# Arm_Driver.net
KiCad netlist of a schematic drawn in EAGLE
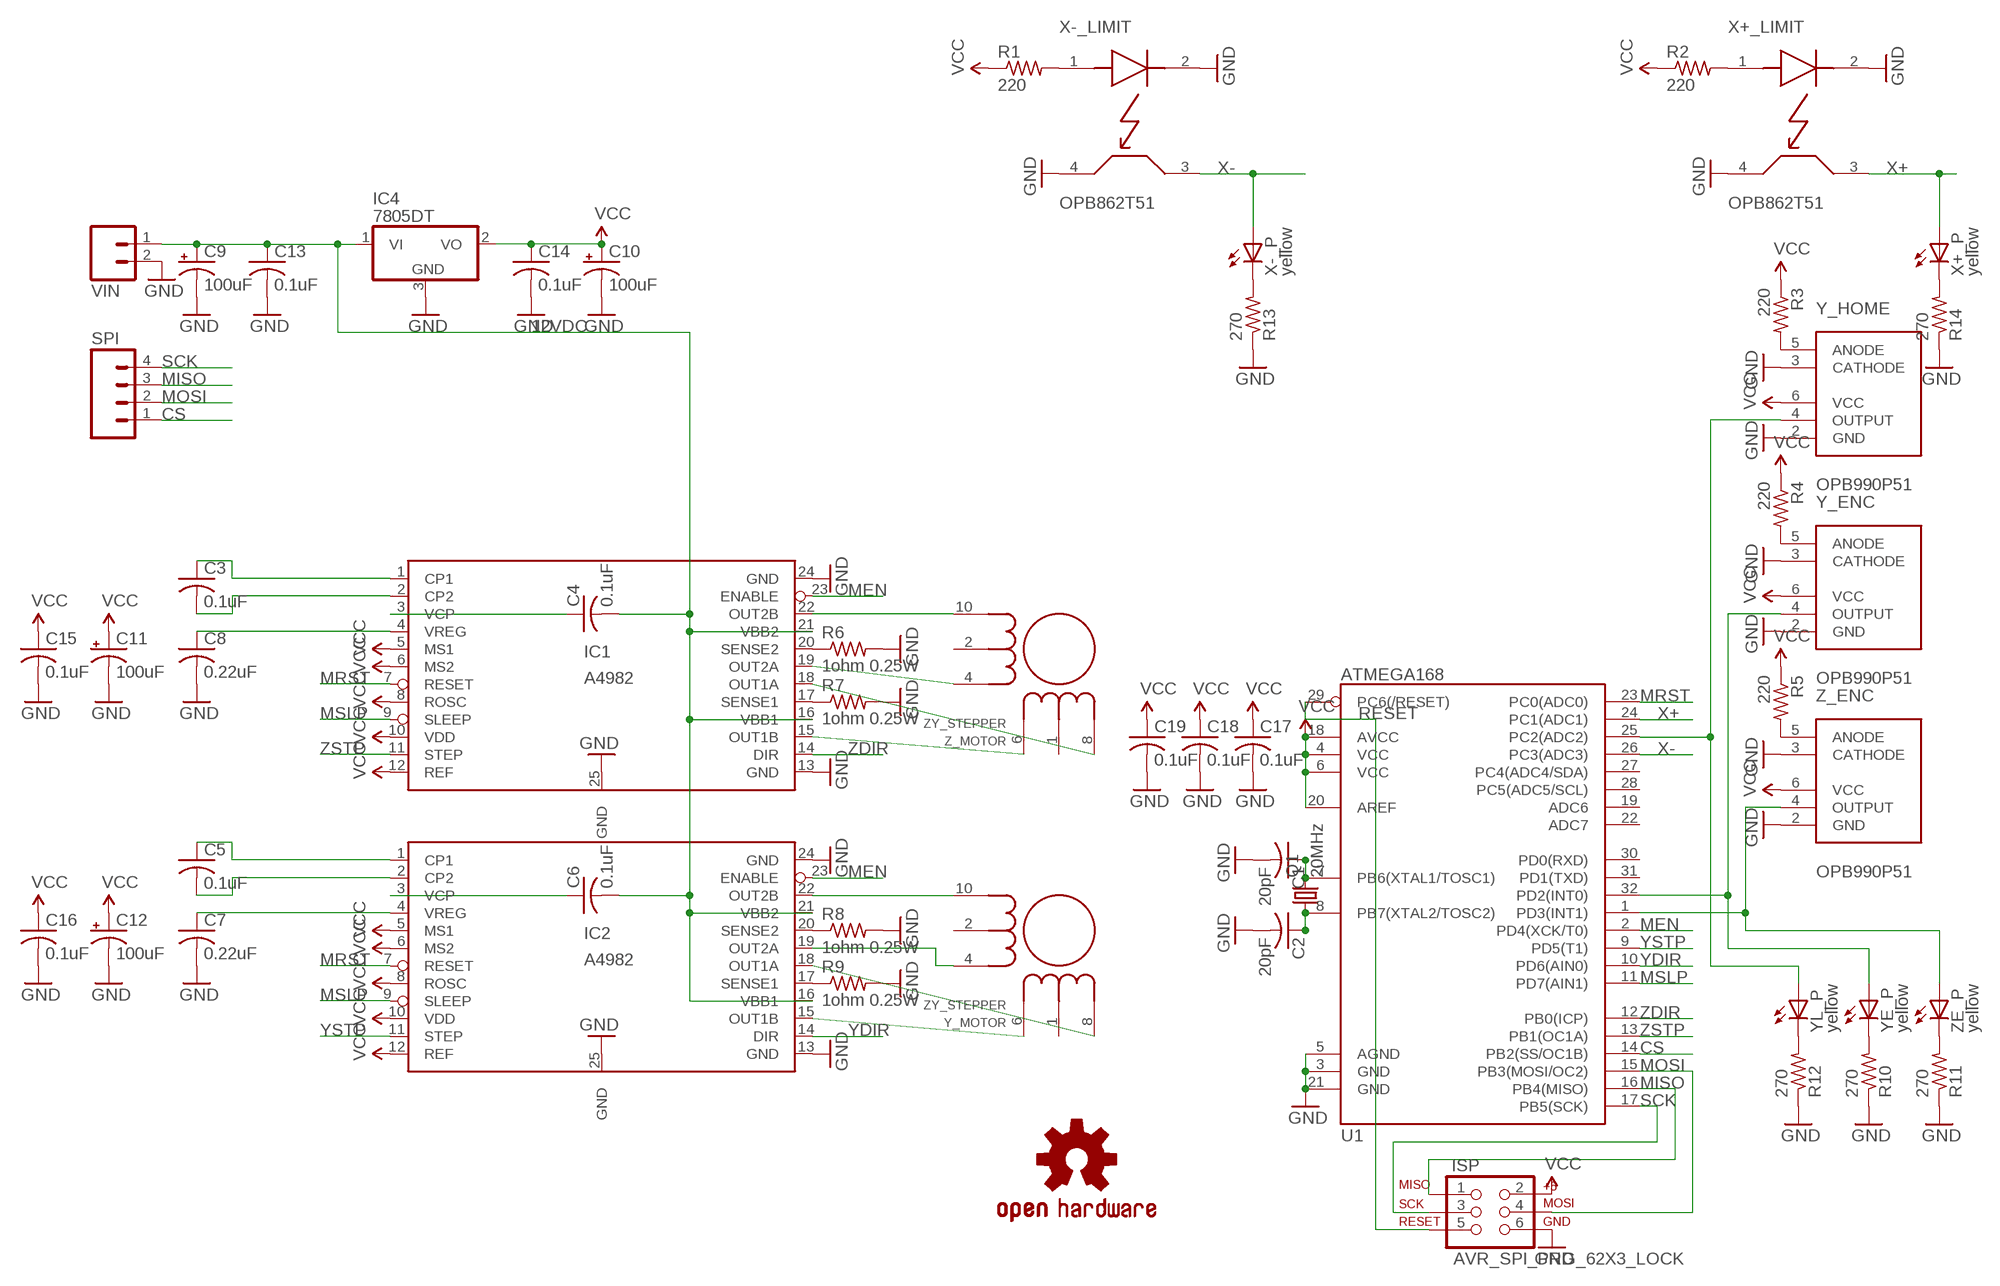
[diagram p0: schematic, sheet 1]

(export (version "E")
  (design (tool "Eeschema 10.0.6"))
  (components
    (comp (ref "C1")
      (value "20pF")
      (footprint "eagle-import:C0603")
      (libsource (lib "eagle-import") (part "C-USC0603"))
    )
    (comp (ref "C2")
      (value "20pF")
      (footprint "eagle-import:C0603")
      (libsource (lib "eagle-import") (part "C-USC0603"))
    )
    (comp (ref "C3")
      (value "0.1uF")
      (footprint "eagle-import:C0603")
      (libsource (lib "eagle-import") (part "C-USC0603"))
    )
    (comp (ref "C4")
      (value "0.1uF")
      (footprint "eagle-import:C0603")
      (libsource (lib "eagle-import") (part "C-USC0603"))
    )
    (comp (ref "C5")
      (value "0.1uF")
      (footprint "eagle-import:C0603")
      (libsource (lib "eagle-import") (part "C-USC0603"))
    )
    (comp (ref "C6")
      (value "0.1uF")
      (footprint "eagle-import:C0603")
      (libsource (lib "eagle-import") (part "C-USC0603"))
    )
    (comp (ref "C7")
      (value "0.22uF")
      (footprint "eagle-import:C0603")
      (libsource (lib "eagle-import") (part "C-USC0603"))
    )
    (comp (ref "C8")
      (value "0.22uF")
      (footprint "eagle-import:C0603")
      (libsource (lib "eagle-import") (part "C-USC0603"))
    )
    (comp (ref "C9")
      (value "100uF")
      (footprint "eagle-import:153CLV-0505")
      (libsource (lib "eagle-import") (part "CPOL-US153CLV-0505"))
    )
    (comp (ref "C10")
      (value "100uF")
      (footprint "eagle-import:153CLV-0505")
      (libsource (lib "eagle-import") (part "CPOL-US153CLV-0505"))
    )
    (comp (ref "C11")
      (value "100uF")
      (footprint "eagle-import:153CLV-0505")
      (libsource (lib "eagle-import") (part "CPOL-US153CLV-0505"))
    )
    (comp (ref "C12")
      (value "100uF")
      (footprint "eagle-import:153CLV-0505")
      (libsource (lib "eagle-import") (part "CPOL-US153CLV-0505"))
    )
    (comp (ref "C13")
      (value "0.1uF")
      (footprint "eagle-import:C0603")
      (libsource (lib "eagle-import") (part "C-USC0603"))
    )
    (comp (ref "C14")
      (value "0.1uF")
      (footprint "eagle-import:C0603")
      (libsource (lib "eagle-import") (part "C-USC0603"))
    )
    (comp (ref "C15")
      (value "0.1uF")
      (footprint "eagle-import:C0603")
      (libsource (lib "eagle-import") (part "C-USC0603"))
    )
    (comp (ref "C16")
      (value "0.1uF")
      (footprint "eagle-import:C0603")
      (libsource (lib "eagle-import") (part "C-USC0603"))
    )
    (comp (ref "C17")
      (value "0.1uF")
      (footprint "eagle-import:C0603")
      (libsource (lib "eagle-import") (part "C-USC0603"))
    )
    (comp (ref "C18")
      (value "0.1uF")
      (footprint "eagle-import:C0603")
      (libsource (lib "eagle-import") (part "C-USC0603"))
    )
    (comp (ref "C19")
      (value "0.1uF")
      (footprint "eagle-import:C0603")
      (libsource (lib "eagle-import") (part "C-USC0603"))
    )
    (comp (ref "IC1")
      (value "A4982")
      (footprint "eagle-import:24TSSOP")
      (libsource (lib "eagle-import") (part "A4982"))
    )
    (comp (ref "IC2")
      (value "A4982")
      (footprint "eagle-import:24TSSOP")
      (libsource (lib "eagle-import") (part "A4982"))
    )
    (comp (ref "IC4")
      (value "7805DT")
      (footprint "eagle-import:TO252")
      (libsource (lib "eagle-import") (part "78DT05"))
    )
    (comp (ref "ISP")
      (value "AVR_SPI_PRG_62X3_LOCK")
      (footprint "eagle-import:2X3_LOCK")
      (libsource (lib "eagle-import") (part "AVR_SPI_PRG_62X3_LOCK"))
    )
    (comp (ref "Q1")
      (value "20MHz")
      (footprint "eagle-import:HC49UP")
      (libsource (lib "eagle-import") (part "CRYSTALHC49UP"))
    )
    (comp (ref "R1")
      (value "220")
      (footprint "eagle-import:R0603")
      (libsource (lib "eagle-import") (part "R-US_R0603"))
    )
    (comp (ref "R2")
      (value "220")
      (footprint "eagle-import:R0603")
      (libsource (lib "eagle-import") (part "R-US_R0603"))
    )
    (comp (ref "R3")
      (value "220")
      (footprint "eagle-import:R0603")
      (libsource (lib "eagle-import") (part "R-US_R0603"))
    )
    (comp (ref "R4")
      (value "220")
      (footprint "eagle-import:R0603")
      (libsource (lib "eagle-import") (part "R-US_R0603"))
    )
    (comp (ref "R5")
      (value "220")
      (footprint "eagle-import:R0603")
      (libsource (lib "eagle-import") (part "R-US_R0603"))
    )
    (comp (ref "R6")
      (value "1ohm 0.25W")
      (footprint "eagle-import:R0603")
      (libsource (lib "eagle-import") (part "R-US_R0603"))
    )
    (comp (ref "R7")
      (value "1ohm 0.25W")
      (footprint "eagle-import:R0603")
      (libsource (lib "eagle-import") (part "R-US_R0603"))
    )
    (comp (ref "R8")
      (value "1ohm 0.25W")
      (footprint "eagle-import:R0603")
      (libsource (lib "eagle-import") (part "R-US_R0603"))
    )
    (comp (ref "R9")
      (value "1ohm 0.25W")
      (footprint "eagle-import:R0603")
      (libsource (lib "eagle-import") (part "R-US_R0603"))
    )
    (comp (ref "R10")
      (value "270")
      (footprint "eagle-import:R0603")
      (libsource (lib "eagle-import") (part "R-US_R0603"))
    )
    (comp (ref "R11")
      (value "270")
      (footprint "eagle-import:R0603")
      (libsource (lib "eagle-import") (part "R-US_R0603"))
    )
    (comp (ref "R12")
      (value "270")
      (footprint "eagle-import:R0603")
      (libsource (lib "eagle-import") (part "R-US_R0603"))
    )
    (comp (ref "R13")
      (value "270")
      (footprint "eagle-import:R0603")
      (libsource (lib "eagle-import") (part "R-US_R0603"))
    )
    (comp (ref "R14")
      (value "270")
      (footprint "eagle-import:R0603")
      (libsource (lib "eagle-import") (part "R-US_R0603"))
    )
    (comp (ref "SPI")
      (value "M04LOCK")
      (footprint "eagle-import:1X04_LOCK")
      (libsource (lib "eagle-import") (part "M04LOCK"))
    )
    (comp (ref "U$1")
      (value "OSHW-LOGOM")
      (footprint "eagle-import:OSHW-LOGO-M")
      (libsource (lib "eagle-import") (part "OSHW-LOGOM"))
    )
    (comp (ref "U1")
      (value "ATMEGA168")
      (footprint "eagle-import:TQFP32-08")
      (libsource (lib "eagle-import") (part "ATMEGA168"))
    )
    (comp (ref "VIN")
      (value "M025MM")
      (footprint "eagle-import:SCREWTERMINAL-5MM-2")
      (libsource (lib "eagle-import") (part "M025MM"))
    )
    (comp (ref "X+_LIMIT")
      (value "OPB862T51")
      (footprint "eagle-import:OPB862T51")
      (libsource (lib "eagle-import") (part "OPB862T51"))
    )
    (comp (ref "X+_P")
      (value "yellow")
      (footprint "eagle-import:CHIP-LED0603")
      (libsource (lib "eagle-import") (part "LEDCHIP-LED0603"))
    )
    (comp (ref "X-_LIMIT")
      (value "OPB862T51")
      (footprint "eagle-import:OPB862T51")
      (libsource (lib "eagle-import") (part "OPB862T51"))
    )
    (comp (ref "X-_P")
      (value "yellow")
      (footprint "eagle-import:CHIP-LED0603")
      (libsource (lib "eagle-import") (part "LEDCHIP-LED0603"))
    )
    (comp (ref "YE_P")
      (value "yellow")
      (footprint "eagle-import:CHIP-LED0603")
      (libsource (lib "eagle-import") (part "LEDCHIP-LED0603"))
    )
    (comp (ref "YL_P")
      (value "yellow")
      (footprint "eagle-import:CHIP-LED0603")
      (libsource (lib "eagle-import") (part "LEDCHIP-LED0603"))
    )
    (comp (ref "Y_ENC")
      (value "OPB990P51")
      (footprint "eagle-import:OPB990P51")
      (libsource (lib "eagle-import") (part "OPB990P51"))
    )
    (comp (ref "Y_HOME")
      (value "OPB990P51")
      (footprint "eagle-import:OPB990P51")
      (libsource (lib "eagle-import") (part "OPB990P51"))
    )
    (comp (ref "Y_MOTOR")
      (value "ZY_STEPPER")
      (footprint "eagle-import:2X5_SHROUDED")
      (libsource (lib "eagle-import") (part "ZY_STEPPER"))
    )
    (comp (ref "ZE_P")
      (value "yellow")
      (footprint "eagle-import:CHIP-LED0603")
      (libsource (lib "eagle-import") (part "LEDCHIP-LED0603"))
    )
    (comp (ref "Z_ENC")
      (value "OPB990P51")
      (footprint "eagle-import:OPB990P51")
      (libsource (lib "eagle-import") (part "OPB990P51"))
    )
    (comp (ref "Z_MOTOR")
      (value "ZY_STEPPER")
      (footprint "eagle-import:2X5_SHROUDED")
      (libsource (lib "eagle-import") (part "ZY_STEPPER"))
    )
  )
  (nets
    (net (code "1") (name "/12VDC") (class "Default")
      (node (ref "C13") (pin "1") (pinfunction "1_1") (pintype "passive"))
      (node (ref "C4") (pin "2") (pinfunction "2_2") (pintype "passive"))
      (node (ref "C6") (pin "2") (pinfunction "2_2") (pintype "passive"))
      (node (ref "C9") (pin "+") (pinfunction "+_+") (pintype "passive"))
      (node (ref "IC1") (pin "16") (pinfunction "VBB1_16") (pintype "power_in"))
      (node (ref "IC1") (pin "21") (pinfunction "VBB2_21") (pintype "power_in"))
      (node (ref "IC2") (pin "16") (pinfunction "VBB1_16") (pintype "power_in"))
      (node (ref "IC2") (pin "21") (pinfunction "VBB2_21") (pintype "power_in"))
      (node (ref "IC4") (pin "1") (pinfunction "VI_1") (pintype "input"))
      (node (ref "VIN") (pin "1") (pinfunction "1_1") (pintype "passive"))
    )
    (net (code "2") (name "/CS") (class "Default")
      (node (ref "SPI") (pin "1") (pinfunction "1_1") (pintype "passive"))
      (node (ref "U1") (pin "14") (pinfunction "PB2(SS/OC1B)_14") (pintype "bidirectional"))
    )
    (net (code "3") (name "/MEN") (class "Default")
      (node (ref "IC1") (pin "23") (pinfunction "ENABLE_23") (pintype "input"))
      (node (ref "IC2") (pin "23") (pinfunction "ENABLE_23") (pintype "input"))
      (node (ref "U1") (pin "2") (pinfunction "PD4(XCK/T0)_2") (pintype "bidirectional"))
    )
    (net (code "4") (name "/MISO") (class "Default")
      (node (ref "ISP") (pin "1") (pinfunction "1_1") (pintype "passive"))
      (node (ref "SPI") (pin "3") (pinfunction "3_3") (pintype "passive"))
      (node (ref "U1") (pin "16") (pinfunction "PB4(MISO)_16") (pintype "bidirectional"))
    )
    (net (code "5") (name "/MOSI") (class "Default")
      (node (ref "ISP") (pin "4") (pinfunction "4_4") (pintype "passive"))
      (node (ref "SPI") (pin "2") (pinfunction "2_2") (pintype "passive"))
      (node (ref "U1") (pin "15") (pinfunction "PB3(MOSI/OC2)_15") (pintype "bidirectional"))
    )
    (net (code "6") (name "/MRST") (class "Default")
      (node (ref "IC1") (pin "7") (pinfunction "RESET_7") (pintype "input"))
      (node (ref "IC2") (pin "7") (pinfunction "RESET_7") (pintype "input"))
      (node (ref "U1") (pin "23") (pinfunction "PC0(ADC0)_23") (pintype "bidirectional"))
    )
    (net (code "7") (name "/MSLP") (class "Default")
      (node (ref "IC1") (pin "9") (pinfunction "SLEEP_9") (pintype "input"))
      (node (ref "IC2") (pin "9") (pinfunction "SLEEP_9") (pintype "input"))
      (node (ref "U1") (pin "11") (pinfunction "PD7(AIN1)_11") (pintype "bidirectional"))
    )
    (net (code "8") (name "/RESET") (class "Default")
      (node (ref "ISP") (pin "5") (pinfunction "5_5") (pintype "passive"))
      (node (ref "U1") (pin "29") (pinfunction "PC6(/RESET)_29") (pintype "bidirectional"))
    )
    (net (code "9") (name "/SCK") (class "Default")
      (node (ref "ISP") (pin "3") (pinfunction "3_3") (pintype "passive"))
      (node (ref "SPI") (pin "4") (pinfunction "4_4") (pintype "passive"))
      (node (ref "U1") (pin "17") (pinfunction "PB5(SCK)_17") (pintype "bidirectional"))
    )
    (net (code "10") (name "/X+") (class "Default")
      (node (ref "U1") (pin "24") (pinfunction "PC1(ADC1)_24") (pintype "bidirectional"))
      (node (ref "X+_LIMIT") (pin "3") (pinfunction "COLLECTOR_3") (pintype "bidirectional"))
      (node (ref "X+_P") (pin "A") (pinfunction "A_A") (pintype "passive"))
    )
    (net (code "11") (name "/X-") (class "Default")
      (node (ref "U1") (pin "26") (pinfunction "PC3(ADC3)_26") (pintype "bidirectional"))
      (node (ref "X-_LIMIT") (pin "3") (pinfunction "COLLECTOR_3") (pintype "bidirectional"))
      (node (ref "X-_P") (pin "A") (pinfunction "A_A") (pintype "passive"))
    )
    (net (code "12") (name "/YDIR") (class "Default")
      (node (ref "IC2") (pin "14") (pinfunction "DIR_14") (pintype "input"))
      (node (ref "U1") (pin "10") (pinfunction "PD6(AIN0)_10") (pintype "bidirectional"))
    )
    (net (code "13") (name "/YSTP") (class "Default")
      (node (ref "IC2") (pin "11") (pinfunction "STEP_11") (pintype "input"))
      (node (ref "U1") (pin "9") (pinfunction "PD5(T1)_9") (pintype "bidirectional"))
    )
    (net (code "14") (name "/ZDIR") (class "Default")
      (node (ref "IC1") (pin "14") (pinfunction "DIR_14") (pintype "input"))
      (node (ref "U1") (pin "12") (pinfunction "PB0(ICP)_12") (pintype "bidirectional"))
    )
    (net (code "15") (name "/ZSTP") (class "Default")
      (node (ref "IC1") (pin "11") (pinfunction "STEP_11") (pintype "input"))
      (node (ref "U1") (pin "13") (pinfunction "PB1(OC1A)_13") (pintype "bidirectional"))
    )
    (net (code "16") (name "GND") (class "Default")
      (node (ref "C1") (pin "2") (pinfunction "2_2") (pintype "passive"))
      (node (ref "C10") (pin "-") (pinfunction "-_-") (pintype "passive"))
      (node (ref "C11") (pin "-") (pinfunction "-_-") (pintype "passive"))
      (node (ref "C12") (pin "-") (pinfunction "-_-") (pintype "passive"))
      (node (ref "C13") (pin "2") (pinfunction "2_2") (pintype "passive"))
      (node (ref "C14") (pin "2") (pinfunction "2_2") (pintype "passive"))
      (node (ref "C15") (pin "2") (pinfunction "2_2") (pintype "passive"))
      (node (ref "C16") (pin "2") (pinfunction "2_2") (pintype "passive"))
      (node (ref "C17") (pin "2") (pinfunction "2_2") (pintype "passive"))
      (node (ref "C18") (pin "2") (pinfunction "2_2") (pintype "passive"))
      (node (ref "C19") (pin "2") (pinfunction "2_2") (pintype "passive"))
      (node (ref "C2") (pin "2") (pinfunction "2_2") (pintype "passive"))
      (node (ref "C7") (pin "2") (pinfunction "2_2") (pintype "passive"))
      (node (ref "C8") (pin "2") (pinfunction "2_2") (pintype "passive"))
      (node (ref "C9") (pin "-") (pinfunction "-_-") (pintype "passive"))
      (node (ref "IC1") (pin "13") (pinfunction "GND_13") (pintype "power_in"))
      (node (ref "IC1") (pin "24") (pinfunction "GND_24") (pintype "power_in"))
      (node (ref "IC1") (pin "25") (pinfunction "GND_25") (pintype "power_in"))
      (node (ref "IC2") (pin "13") (pinfunction "GND_13") (pintype "power_in"))
      (node (ref "IC2") (pin "24") (pinfunction "GND_24") (pintype "power_in"))
      (node (ref "IC2") (pin "25") (pinfunction "GND_25") (pintype "power_in"))
      (node (ref "IC4") (pin "3") (pinfunction "GND_3") (pintype "passive"))
      (node (ref "ISP") (pin "6") (pinfunction "6_6") (pintype "passive"))
      (node (ref "R10") (pin "1") (pinfunction "1_1") (pintype "passive"))
      (node (ref "R11") (pin "1") (pinfunction "1_1") (pintype "passive"))
      (node (ref "R12") (pin "1") (pinfunction "1_1") (pintype "passive"))
      (node (ref "R13") (pin "1") (pinfunction "1_1") (pintype "passive"))
      (node (ref "R14") (pin "1") (pinfunction "1_1") (pintype "passive"))
      (node (ref "R6") (pin "2") (pinfunction "2_2") (pintype "passive"))
      (node (ref "R7") (pin "2") (pinfunction "2_2") (pintype "passive"))
      (node (ref "R8") (pin "2") (pinfunction "2_2") (pintype "passive"))
      (node (ref "R9") (pin "2") (pinfunction "2_2") (pintype "passive"))
      (node (ref "U1") (pin "21") (pinfunction "GND_21") (pintype "bidirectional"))
      (node (ref "U1") (pin "3") (pinfunction "GND_3") (pintype "bidirectional"))
      (node (ref "U1") (pin "5") (pinfunction "AGND_5") (pintype "bidirectional"))
      (node (ref "VIN") (pin "2") (pinfunction "2_2") (pintype "passive"))
      (node (ref "X+_LIMIT") (pin "2") (pinfunction "CATHODE_2") (pintype "bidirectional"))
      (node (ref "X+_LIMIT") (pin "4") (pinfunction "EMITTER_4") (pintype "bidirectional"))
      (node (ref "X-_LIMIT") (pin "2") (pinfunction "CATHODE_2") (pintype "bidirectional"))
      (node (ref "X-_LIMIT") (pin "4") (pinfunction "EMITTER_4") (pintype "bidirectional"))
      (node (ref "Y_ENC") (pin "2") (pinfunction "GND_2") (pintype "bidirectional"))
      (node (ref "Y_ENC") (pin "3") (pinfunction "CATHODE_3") (pintype "bidirectional"))
      (node (ref "Y_HOME") (pin "2") (pinfunction "GND_2") (pintype "bidirectional"))
      (node (ref "Y_HOME") (pin "3") (pinfunction "CATHODE_3") (pintype "bidirectional"))
      (node (ref "Z_ENC") (pin "2") (pinfunction "GND_2") (pintype "bidirectional"))
      (node (ref "Z_ENC") (pin "3") (pinfunction "CATHODE_3") (pintype "bidirectional"))
    )
    (net (code "17") (name "Net-(IC1-CP1)") (class "Default")
      (node (ref "C3") (pin "1") (pinfunction "1_1") (pintype "passive"))
      (node (ref "IC1") (pin "1") (pinfunction "CP1_1") (pintype "bidirectional"))
    )
    (net (code "18") (name "Net-(IC1-CP2)") (class "Default")
      (node (ref "C3") (pin "2") (pinfunction "2_2") (pintype "passive"))
      (node (ref "IC1") (pin "2") (pinfunction "CP2_2") (pintype "bidirectional"))
    )
    (net (code "19") (name "Net-(IC1-OUT1A)") (class "Default")
      (node (ref "IC1") (pin "18") (pinfunction "OUT1A_18") (pintype "output"))
      (node (ref "Z_MOTOR") (pin "8") (pinfunction "A1_8") (pintype "bidirectional"))
    )
    (net (code "20") (name "Net-(IC1-OUT1B)") (class "Default")
      (node (ref "IC1") (pin "15") (pinfunction "OUT1B_15") (pintype "output"))
      (node (ref "Z_MOTOR") (pin "6") (pinfunction "A2_6") (pintype "bidirectional"))
    )
    (net (code "21") (name "Net-(IC1-OUT2A)") (class "Default")
      (node (ref "IC1") (pin "19") (pinfunction "OUT2A_19") (pintype "output"))
      (node (ref "Z_MOTOR") (pin "4") (pinfunction "B1_4") (pintype "bidirectional"))
    )
    (net (code "22") (name "Net-(IC1-OUT2B)") (class "Default")
      (node (ref "IC1") (pin "22") (pinfunction "OUT2B_22") (pintype "output"))
      (node (ref "Z_MOTOR") (pin "10") (pinfunction "B2_10") (pintype "bidirectional"))
    )
    (net (code "23") (name "Net-(IC1-SENSE1)") (class "Default")
      (node (ref "IC1") (pin "17") (pinfunction "SENSE1_17") (pintype "input"))
      (node (ref "R7") (pin "1") (pinfunction "1_1") (pintype "passive"))
    )
    (net (code "24") (name "Net-(IC1-SENSE2)") (class "Default")
      (node (ref "IC1") (pin "20") (pinfunction "SENSE2_20") (pintype "input"))
      (node (ref "R6") (pin "1") (pinfunction "1_1") (pintype "passive"))
    )
    (net (code "25") (name "Net-(IC1-VCP)") (class "Default")
      (node (ref "C4") (pin "1") (pinfunction "1_1") (pintype "passive"))
      (node (ref "IC1") (pin "3") (pinfunction "VCP_3") (pintype "bidirectional"))
    )
    (net (code "26") (name "Net-(IC1-VREG)") (class "Default")
      (node (ref "C8") (pin "1") (pinfunction "1_1") (pintype "passive"))
      (node (ref "IC1") (pin "4") (pinfunction "VREG_4") (pintype "bidirectional"))
    )
    (net (code "27") (name "Net-(IC2-CP1)") (class "Default")
      (node (ref "C5") (pin "1") (pinfunction "1_1") (pintype "passive"))
      (node (ref "IC2") (pin "1") (pinfunction "CP1_1") (pintype "bidirectional"))
    )
    (net (code "28") (name "Net-(IC2-CP2)") (class "Default")
      (node (ref "C5") (pin "2") (pinfunction "2_2") (pintype "passive"))
      (node (ref "IC2") (pin "2") (pinfunction "CP2_2") (pintype "bidirectional"))
    )
    (net (code "29") (name "Net-(IC2-OUT1A)") (class "Default")
      (node (ref "IC2") (pin "18") (pinfunction "OUT1A_18") (pintype "output"))
      (node (ref "Y_MOTOR") (pin "8") (pinfunction "A1_8") (pintype "bidirectional"))
    )
    (net (code "30") (name "Net-(IC2-OUT1B)") (class "Default")
      (node (ref "IC2") (pin "15") (pinfunction "OUT1B_15") (pintype "output"))
      (node (ref "Y_MOTOR") (pin "6") (pinfunction "A2_6") (pintype "bidirectional"))
    )
    (net (code "31") (name "Net-(IC2-OUT2A)") (class "Default")
      (node (ref "IC2") (pin "19") (pinfunction "OUT2A_19") (pintype "output"))
      (node (ref "Y_MOTOR") (pin "4") (pinfunction "B1_4") (pintype "bidirectional"))
    )
    (net (code "32") (name "Net-(IC2-OUT2B)") (class "Default")
      (node (ref "IC2") (pin "22") (pinfunction "OUT2B_22") (pintype "output"))
      (node (ref "Y_MOTOR") (pin "10") (pinfunction "B2_10") (pintype "bidirectional"))
    )
    (net (code "33") (name "Net-(IC2-SENSE1)") (class "Default")
      (node (ref "IC2") (pin "17") (pinfunction "SENSE1_17") (pintype "input"))
      (node (ref "R9") (pin "1") (pinfunction "1_1") (pintype "passive"))
    )
    (net (code "34") (name "Net-(IC2-SENSE2)") (class "Default")
      (node (ref "IC2") (pin "20") (pinfunction "SENSE2_20") (pintype "input"))
      (node (ref "R8") (pin "1") (pinfunction "1_1") (pintype "passive"))
    )
    (net (code "35") (name "Net-(IC2-VCP)") (class "Default")
      (node (ref "C6") (pin "1") (pinfunction "1_1") (pintype "passive"))
      (node (ref "IC2") (pin "3") (pinfunction "VCP_3") (pintype "bidirectional"))
    )
    (net (code "36") (name "Net-(IC2-VREG)") (class "Default")
      (node (ref "C7") (pin "1") (pinfunction "1_1") (pintype "passive"))
      (node (ref "IC2") (pin "4") (pinfunction "VREG_4") (pintype "bidirectional"))
    )
    (net (code "37") (name "Net-(R10-Pad2)") (class "Default")
      (node (ref "R10") (pin "2") (pinfunction "2_2") (pintype "passive"))
      (node (ref "YE_P") (pin "C") (pinfunction "C_C") (pintype "passive"))
    )
    (net (code "38") (name "Net-(R11-Pad2)") (class "Default")
      (node (ref "R11") (pin "2") (pinfunction "2_2") (pintype "passive"))
      (node (ref "ZE_P") (pin "C") (pinfunction "C_C") (pintype "passive"))
    )
    (net (code "39") (name "Net-(R12-Pad2)") (class "Default")
      (node (ref "R12") (pin "2") (pinfunction "2_2") (pintype "passive"))
      (node (ref "YL_P") (pin "C") (pinfunction "C_C") (pintype "passive"))
    )
    (net (code "40") (name "Net-(R13-Pad2)") (class "Default")
      (node (ref "R13") (pin "2") (pinfunction "2_2") (pintype "passive"))
      (node (ref "X-_P") (pin "C") (pinfunction "C_C") (pintype "passive"))
    )
    (net (code "41") (name "Net-(R14-Pad2)") (class "Default")
      (node (ref "R14") (pin "2") (pinfunction "2_2") (pintype "passive"))
      (node (ref "X+_P") (pin "C") (pinfunction "C_C") (pintype "passive"))
    )
    (net (code "42") (name "Net-(U1-PB6(XTAL1{slash}TOSC1))") (class "Default")
      (node (ref "C1") (pin "1") (pinfunction "1_1") (pintype "passive"))
      (node (ref "Q1") (pin "2") (pinfunction "2_2") (pintype "passive"))
      (node (ref "U1") (pin "7") (pinfunction "PB6(XTAL1/TOSC1)_7") (pintype "bidirectional"))
    )
    (net (code "43") (name "Net-(U1-PB7(XTAL2{slash}TOSC2))") (class "Default")
      (node (ref "C2") (pin "1") (pinfunction "1_1") (pintype "passive"))
      (node (ref "Q1") (pin "1") (pinfunction "1_1") (pintype "passive"))
      (node (ref "U1") (pin "8") (pinfunction "PB7(XTAL2/TOSC2)_8") (pintype "bidirectional"))
    )
    (net (code "44") (name "Net-(U1-PC2(ADC2))") (class "Default")
      (node (ref "U1") (pin "25") (pinfunction "PC2(ADC2)_25") (pintype "bidirectional"))
      (node (ref "YL_P") (pin "A") (pinfunction "A_A") (pintype "passive"))
      (node (ref "Y_HOME") (pin "4") (pinfunction "OUTPUT_4") (pintype "bidirectional"))
    )
    (net (code "45") (name "Net-(U1-PD2(INT0))") (class "Default")
      (node (ref "U1") (pin "32") (pinfunction "PD2(INT0)_32") (pintype "bidirectional"))
      (node (ref "YE_P") (pin "A") (pinfunction "A_A") (pintype "passive"))
      (node (ref "Y_ENC") (pin "4") (pinfunction "OUTPUT_4") (pintype "bidirectional"))
    )
    (net (code "46") (name "Net-(U1-PD3(INT1))") (class "Default")
      (node (ref "U1") (pin "1") (pinfunction "PD3(INT1)_1") (pintype "bidirectional"))
      (node (ref "ZE_P") (pin "A") (pinfunction "A_A") (pintype "passive"))
      (node (ref "Z_ENC") (pin "4") (pinfunction "OUTPUT_4") (pintype "bidirectional"))
    )
    (net (code "47") (name "Net-(X+_LIMIT-ANODE)") (class "Default")
      (node (ref "R2") (pin "2") (pinfunction "2_2") (pintype "passive"))
      (node (ref "X+_LIMIT") (pin "1") (pinfunction "ANODE_1") (pintype "bidirectional"))
    )
    (net (code "48") (name "Net-(X-_LIMIT-ANODE)") (class "Default")
      (node (ref "R1") (pin "2") (pinfunction "2_2") (pintype "passive"))
      (node (ref "X-_LIMIT") (pin "1") (pinfunction "ANODE_1") (pintype "bidirectional"))
    )
    (net (code "49") (name "Net-(Y_ENC-ANODE)") (class "Default")
      (node (ref "R4") (pin "2") (pinfunction "2_2") (pintype "passive"))
      (node (ref "Y_ENC") (pin "5") (pinfunction "ANODE_5") (pintype "bidirectional"))
    )
    (net (code "50") (name "Net-(Y_HOME-ANODE)") (class "Default")
      (node (ref "R3") (pin "2") (pinfunction "2_2") (pintype "passive"))
      (node (ref "Y_HOME") (pin "5") (pinfunction "ANODE_5") (pintype "bidirectional"))
    )
    (net (code "51") (name "Net-(Z_ENC-ANODE)") (class "Default")
      (node (ref "R5") (pin "2") (pinfunction "2_2") (pintype "passive"))
      (node (ref "Z_ENC") (pin "5") (pinfunction "ANODE_5") (pintype "bidirectional"))
    )
    (net (code "52") (name "VCC") (class "Default")
      (node (ref "C10") (pin "+") (pinfunction "+_+") (pintype "passive"))
      (node (ref "C11") (pin "+") (pinfunction "+_+") (pintype "passive"))
      (node (ref "C12") (pin "+") (pinfunction "+_+") (pintype "passive"))
      (node (ref "C14") (pin "1") (pinfunction "1_1") (pintype "passive"))
      (node (ref "C15") (pin "1") (pinfunction "1_1") (pintype "passive"))
      (node (ref "C16") (pin "1") (pinfunction "1_1") (pintype "passive"))
      (node (ref "C17") (pin "1") (pinfunction "1_1") (pintype "passive"))
      (node (ref "C18") (pin "1") (pinfunction "1_1") (pintype "passive"))
      (node (ref "C19") (pin "1") (pinfunction "1_1") (pintype "passive"))
      (node (ref "IC1") (pin "10") (pinfunction "VDD_10") (pintype "power_in"))
      (node (ref "IC1") (pin "12") (pinfunction "REF_12") (pintype "input"))
      (node (ref "IC1") (pin "5") (pinfunction "MS1_5") (pintype "input"))
      (node (ref "IC1") (pin "6") (pinfunction "MS2_6") (pintype "input"))
      (node (ref "IC1") (pin "8") (pinfunction "ROSC_8") (pintype "bidirectional"))
      (node (ref "IC2") (pin "10") (pinfunction "VDD_10") (pintype "power_in"))
      (node (ref "IC2") (pin "12") (pinfunction "REF_12") (pintype "input"))
      (node (ref "IC2") (pin "5") (pinfunction "MS1_5") (pintype "input"))
      (node (ref "IC2") (pin "6") (pinfunction "MS2_6") (pintype "input"))
      (node (ref "IC2") (pin "8") (pinfunction "ROSC_8") (pintype "bidirectional"))
      (node (ref "IC4") (pin "2") (pinfunction "VO_2") (pintype "passive"))
      (node (ref "ISP") (pin "2") (pinfunction "2_2") (pintype "passive"))
      (node (ref "R1") (pin "1") (pinfunction "1_1") (pintype "passive"))
      (node (ref "R2") (pin "1") (pinfunction "1_1") (pintype "passive"))
      (node (ref "R3") (pin "1") (pinfunction "1_1") (pintype "passive"))
      (node (ref "R4") (pin "1") (pinfunction "1_1") (pintype "passive"))
      (node (ref "R5") (pin "1") (pinfunction "1_1") (pintype "passive"))
      (node (ref "U1") (pin "18") (pinfunction "AVCC_18") (pintype "bidirectional"))
      (node (ref "U1") (pin "20") (pinfunction "AREF_20") (pintype "bidirectional"))
      (node (ref "U1") (pin "4") (pinfunction "VCC_4") (pintype "bidirectional"))
      (node (ref "U1") (pin "6") (pinfunction "VCC_6") (pintype "bidirectional"))
      (node (ref "Y_ENC") (pin "6") (pinfunction "VCC_6") (pintype "bidirectional"))
      (node (ref "Y_HOME") (pin "6") (pinfunction "VCC_6") (pintype "bidirectional"))
      (node (ref "Z_ENC") (pin "6") (pinfunction "VCC_6") (pintype "bidirectional"))
    )
    (net (code "53") (name "unconnected-(U1-ADC6-Pad19)") (class "Default")
      (node (ref "U1") (pin "19") (pinfunction "ADC6_19") (pintype "bidirectional"))
    )
    (net (code "54") (name "unconnected-(U1-ADC7-Pad22)") (class "Default")
      (node (ref "U1") (pin "22") (pinfunction "ADC7_22") (pintype "bidirectional"))
    )
    (net (code "55") (name "unconnected-(U1-PC4(ADC4{slash}SDA)-Pad27)") (class "Default")
      (node (ref "U1") (pin "27") (pinfunction "PC4(ADC4/SDA)_27") (pintype "bidirectional"))
    )
    (net (code "56") (name "unconnected-(U1-PC5(ADC5{slash}SCL)-Pad28)") (class "Default")
      (node (ref "U1") (pin "28") (pinfunction "PC5(ADC5/SCL)_28") (pintype "bidirectional"))
    )
    (net (code "57") (name "unconnected-(U1-PD0(RXD)-Pad30)") (class "Default")
      (node (ref "U1") (pin "30") (pinfunction "PD0(RXD)_30") (pintype "bidirectional"))
    )
    (net (code "58") (name "unconnected-(U1-PD1(TXD)-Pad31)") (class "Default")
      (node (ref "U1") (pin "31") (pinfunction "PD1(TXD)_31") (pintype "bidirectional"))
    )
    (net (code "59") (name "unconnected-(Y_MOTOR-CA-Pad1)") (class "Default")
      (node (ref "Y_MOTOR") (pin "1") (pinfunction "CA_1") (pintype "bidirectional"))
    )
    (net (code "60") (name "unconnected-(Y_MOTOR-CB-Pad2)") (class "Default")
      (node (ref "Y_MOTOR") (pin "2") (pinfunction "CB_2") (pintype "bidirectional"))
    )
    (net (code "61") (name "unconnected-(Z_MOTOR-CA-Pad1)") (class "Default")
      (node (ref "Z_MOTOR") (pin "1") (pinfunction "CA_1") (pintype "bidirectional"))
    )
    (net (code "62") (name "unconnected-(Z_MOTOR-CB-Pad2)") (class "Default")
      (node (ref "Z_MOTOR") (pin "2") (pinfunction "CB_2") (pintype "bidirectional"))
    )
  )
)
